# Sensor_room.net
KiCad netlist of a schematic drawn in EAGLE
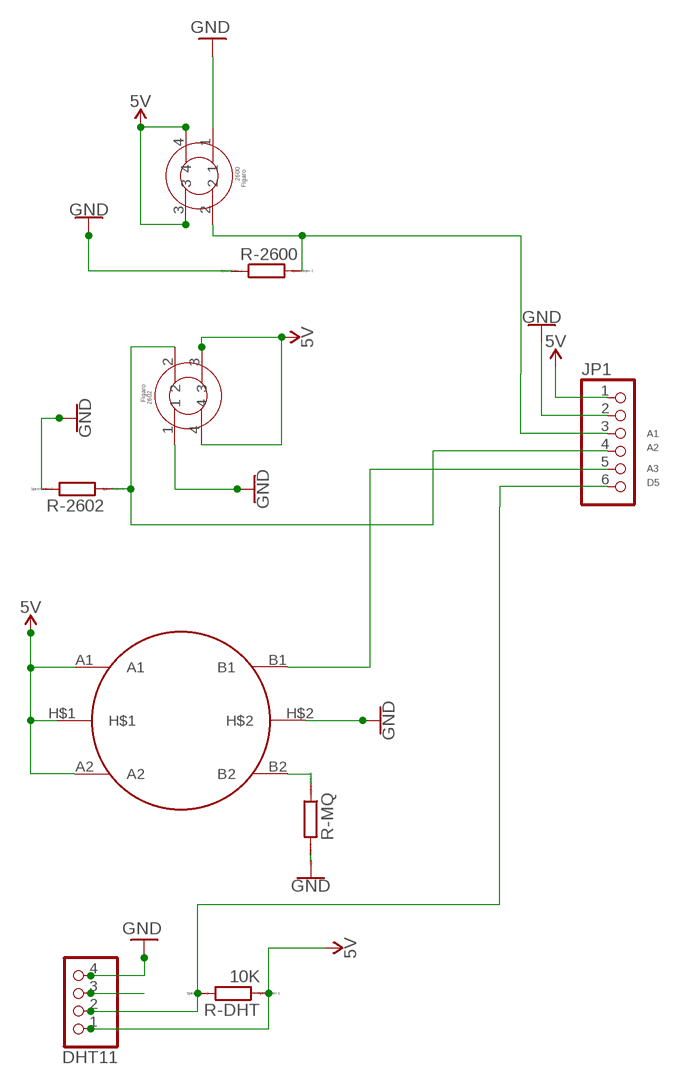
[diagram p0: schematic, sheet 1]

(export (version "E")
  (design (tool "Eeschema 10.0.6"))
  (components
    (comp (ref "2600")
      (value "FIGARO2602")
      (footprint "eagle-import:FIGARO2602")
      (libsource (lib "eagle-import") (part "FIGARO2602"))
    )
    (comp (ref "2602")
      (value "FIGARO2602")
      (footprint "eagle-import:FIGARO2602")
      (libsource (lib "eagle-import") (part "FIGARO2602"))
    )
    (comp (ref "DHT11")
      (value "PINHD-1X4")
      (footprint "eagle-import:1X04")
      (libsource (lib "eagle-import") (part "PINHD-1X4"))
    )
    (comp (ref "JP1")
      (value "PINHD-1X6CB")
      (footprint "eagle-import:1X06-CLEANBIG")
      (libsource (lib "eagle-import") (part "PINHD-1X6CB"))
    )
    (comp (ref "MQ-135")
      (value "MQ_135_A")
      (footprint "eagle-import:MQ-135")
      (libsource (lib "eagle-import") (part "MQ_135_A"))
    )
    (comp (ref "R-2600")
      (value "R0207/10")
      (footprint "eagle-import:0207_10")
      (libsource (lib "eagle-import") (part "R0207/10"))
    )
    (comp (ref "R-2602")
      (value "R0207/10")
      (footprint "eagle-import:0207_10")
      (libsource (lib "eagle-import") (part "R0207/10"))
    )
    (comp (ref "R-DHT")
      (value "10K")
      (footprint "eagle-import:0207_10")
      (libsource (lib "eagle-import") (part "R0207/10"))
    )
    (comp (ref "R-MQ")
      (value "R0207/10")
      (footprint "eagle-import:0207_10")
      (libsource (lib "eagle-import") (part "R0207/10"))
    )
  )
  (nets
    (net (code "1") (name "5V") (class "Default")
      (node (ref "2600") (pin "3") (pinfunction "4_3") (pintype "bidirectional"))
      (node (ref "2600") (pin "4") (pinfunction "3_4") (pintype "bidirectional"))
      (node (ref "2602") (pin "3") (pinfunction "4_3") (pintype "bidirectional"))
      (node (ref "2602") (pin "4") (pinfunction "3_4") (pintype "bidirectional"))
      (node (ref "DHT11") (pin "1") (pinfunction "1_1") (pintype "passive"))
      (node (ref "JP1") (pin "1") (pinfunction "1_1") (pintype "passive"))
      (node (ref "MQ-135") (pin "A1") (pinfunction "A1_A1") (pintype "bidirectional"))
      (node (ref "MQ-135") (pin "A2") (pinfunction "A2_A2") (pintype "bidirectional"))
      (node (ref "MQ-135") (pin "H$1") (pinfunction "H$1_H$1") (pintype "bidirectional"))
      (node (ref "R-DHT") (pin "1") (pinfunction "1_1") (pintype "passive"))
    )
    (net (code "2") (name "GND") (class "Default")
      (node (ref "2600") (pin "1") (pinfunction "2_1") (pintype "bidirectional"))
      (node (ref "2602") (pin "1") (pinfunction "2_1") (pintype "bidirectional"))
      (node (ref "DHT11") (pin "4") (pinfunction "4_4") (pintype "passive"))
      (node (ref "JP1") (pin "2") (pinfunction "2_2") (pintype "passive"))
      (node (ref "MQ-135") (pin "H$2") (pinfunction "H$2_H$2") (pintype "bidirectional"))
      (node (ref "R-2600") (pin "1") (pinfunction "1_1") (pintype "passive"))
      (node (ref "R-2602") (pin "2") (pinfunction "2_2") (pintype "passive"))
      (node (ref "R-MQ") (pin "2") (pinfunction "2_2") (pintype "passive"))
    )
    (net (code "3") (name "Net-(2600-1)") (class "Default")
      (node (ref "2600") (pin "2") (pinfunction "1_2") (pintype "bidirectional"))
      (node (ref "JP1") (pin "3") (pinfunction "3_3") (pintype "passive"))
      (node (ref "R-2600") (pin "2") (pinfunction "2_2") (pintype "passive"))
    )
    (net (code "4") (name "Net-(2602-1)") (class "Default")
      (node (ref "2602") (pin "2") (pinfunction "1_2") (pintype "bidirectional"))
      (node (ref "JP1") (pin "4") (pinfunction "4_4") (pintype "passive"))
      (node (ref "R-2602") (pin "1") (pinfunction "1_1") (pintype "passive"))
    )
    (net (code "5") (name "Net-(DHT11-Pad2)") (class "Default")
      (node (ref "DHT11") (pin "2") (pinfunction "2_2") (pintype "passive"))
      (node (ref "JP1") (pin "6") (pinfunction "6_6") (pintype "passive"))
      (node (ref "R-DHT") (pin "2") (pinfunction "2_2") (pintype "passive"))
    )
    (net (code "6") (name "Net-(JP1-Pad5)") (class "Default")
      (node (ref "JP1") (pin "5") (pinfunction "5_5") (pintype "passive"))
      (node (ref "MQ-135") (pin "B1") (pinfunction "B1_B1") (pintype "bidirectional"))
    )
    (net (code "7") (name "Net-(MQ-135-PadB2)") (class "Default")
      (node (ref "MQ-135") (pin "B2") (pinfunction "B2_B2") (pintype "bidirectional"))
      (node (ref "R-MQ") (pin "1") (pinfunction "1_1") (pintype "passive"))
    )
    (net (code "8") (name "unconnected-(DHT11-Pad3)") (class "Default")
      (node (ref "DHT11") (pin "3") (pinfunction "3_3") (pintype "passive"))
    )
  )
)
